# LED1.net
KiCad netlist of a schematic drawn in EAGLE
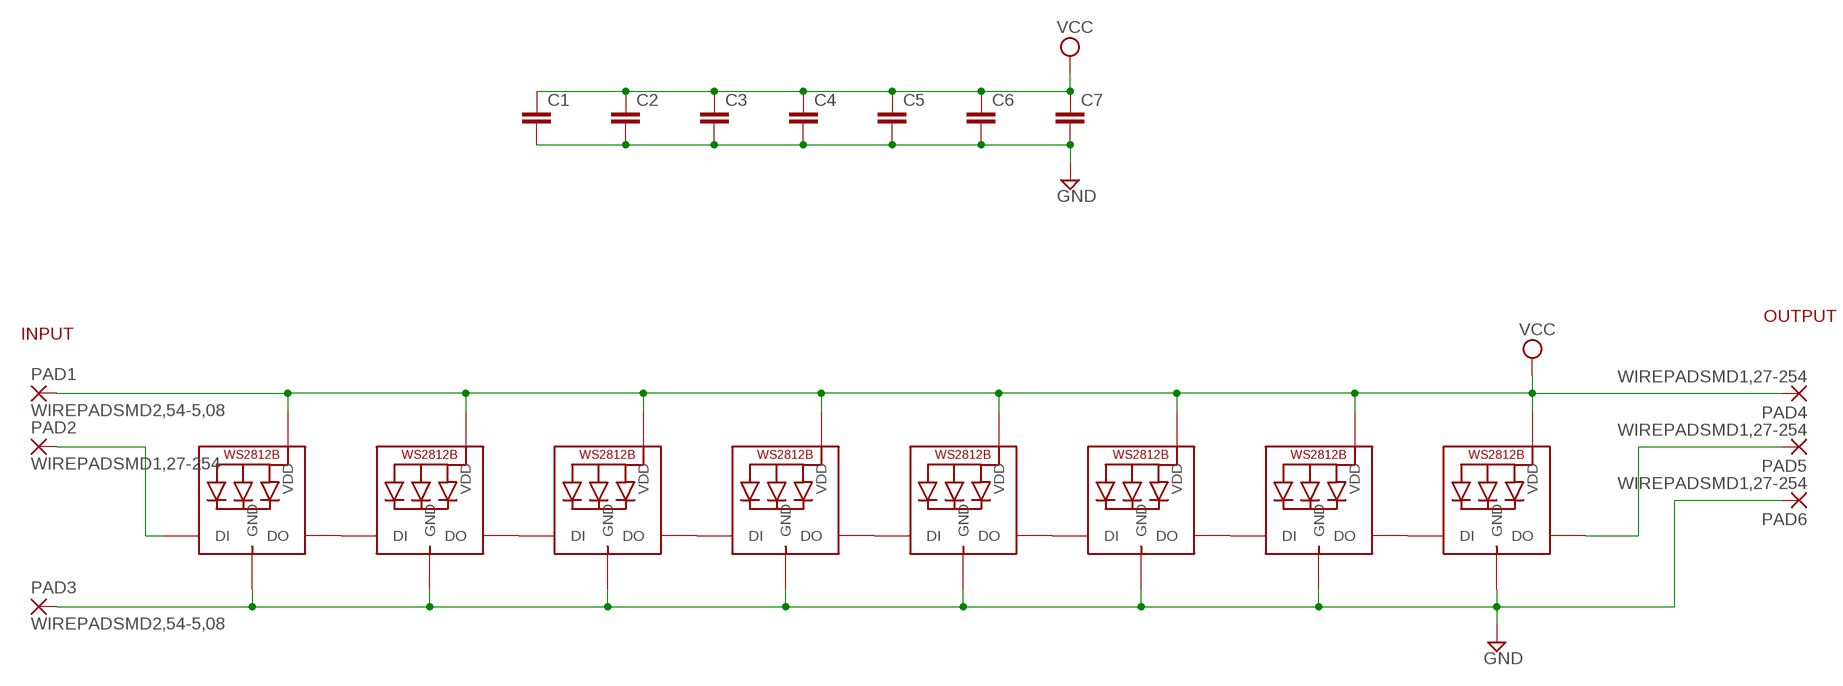
[diagram p0: schematic, sheet 1]

(export (version "E")
  (design (tool "Eeschema 10.0.6"))
  (components
    (comp (ref "C1")
      (value "C-EUC0805K")
      (footprint "eagle-import:C0805K")
      (libsource (lib "eagle-import") (part "C-EUC0805K"))
    )
    (comp (ref "C2")
      (value "C-EUC0805K")
      (footprint "eagle-import:C0805K")
      (libsource (lib "eagle-import") (part "C-EUC0805K"))
    )
    (comp (ref "C3")
      (value "C-EUC0805K")
      (footprint "eagle-import:C0805K")
      (libsource (lib "eagle-import") (part "C-EUC0805K"))
    )
    (comp (ref "C4")
      (value "C-EUC0805K")
      (footprint "eagle-import:C0805K")
      (libsource (lib "eagle-import") (part "C-EUC0805K"))
    )
    (comp (ref "C5")
      (value "C-EUC0805K")
      (footprint "eagle-import:C0805K")
      (libsource (lib "eagle-import") (part "C-EUC0805K"))
    )
    (comp (ref "C6")
      (value "C-EUC0805K")
      (footprint "eagle-import:C0805K")
      (libsource (lib "eagle-import") (part "C-EUC0805K"))
    )
    (comp (ref "C7")
      (value "C-EUC0805K")
      (footprint "eagle-import:C0805K")
      (libsource (lib "eagle-import") (part "C-EUC0805K"))
    )
    (comp (ref "LED1")
      (value "WS2812B5050")
      (footprint "eagle-import:WS2812B")
      (libsource (lib "eagle-import") (part "WS2812B5050"))
    )
    (comp (ref "LED2")
      (value "WS2812B5050")
      (footprint "eagle-import:WS2812B")
      (libsource (lib "eagle-import") (part "WS2812B5050"))
    )
    (comp (ref "LED3")
      (value "WS2812B5050")
      (footprint "eagle-import:WS2812B")
      (libsource (lib "eagle-import") (part "WS2812B5050"))
    )
    (comp (ref "LED4")
      (value "WS2812B5050")
      (footprint "eagle-import:WS2812B")
      (libsource (lib "eagle-import") (part "WS2812B5050"))
    )
    (comp (ref "LED5")
      (value "WS2812B5050")
      (footprint "eagle-import:WS2812B")
      (libsource (lib "eagle-import") (part "WS2812B5050"))
    )
    (comp (ref "LED6")
      (value "WS2812B5050")
      (footprint "eagle-import:WS2812B")
      (libsource (lib "eagle-import") (part "WS2812B5050"))
    )
    (comp (ref "LED7")
      (value "WS2812B5050")
      (footprint "eagle-import:WS2812B")
      (libsource (lib "eagle-import") (part "WS2812B5050"))
    )
    (comp (ref "LED8")
      (value "WS2812B5050")
      (footprint "eagle-import:WS2812B")
      (libsource (lib "eagle-import") (part "WS2812B5050"))
    )
    (comp (ref "PAD1")
      (value "WIREPADSMD2,54-5,08")
      (footprint "eagle-import:SMD2,54-5,08")
      (libsource (lib "eagle-import") (part "WIREPADSMD2,54-5,08"))
    )
    (comp (ref "PAD2")
      (value "WIREPADSMD1,27-254")
      (footprint "eagle-import:SMD1,27-2,54")
      (libsource (lib "eagle-import") (part "WIREPADSMD1,27-254"))
    )
    (comp (ref "PAD3")
      (value "WIREPADSMD2,54-5,08")
      (footprint "eagle-import:SMD2,54-5,08")
      (libsource (lib "eagle-import") (part "WIREPADSMD2,54-5,08"))
    )
    (comp (ref "PAD4")
      (value "WIREPADSMD1,27-254")
      (footprint "eagle-import:SMD1,27-2,54")
      (libsource (lib "eagle-import") (part "WIREPADSMD1,27-254"))
    )
    (comp (ref "PAD5")
      (value "WIREPADSMD1,27-254")
      (footprint "eagle-import:SMD1,27-2,54")
      (libsource (lib "eagle-import") (part "WIREPADSMD1,27-254"))
    )
    (comp (ref "PAD6")
      (value "WIREPADSMD1,27-254")
      (footprint "eagle-import:SMD1,27-2,54")
      (libsource (lib "eagle-import") (part "WIREPADSMD1,27-254"))
    )
  )
  (nets
    (net (code "1") (name "GND") (class "Default")
      (node (ref "C1") (pin "2") (pinfunction "2_2") (pintype "passive"))
      (node (ref "C2") (pin "2") (pinfunction "2_2") (pintype "passive"))
      (node (ref "C3") (pin "2") (pinfunction "2_2") (pintype "passive"))
      (node (ref "C4") (pin "2") (pinfunction "2_2") (pintype "passive"))
      (node (ref "C5") (pin "2") (pinfunction "2_2") (pintype "passive"))
      (node (ref "C6") (pin "2") (pinfunction "2_2") (pintype "passive"))
      (node (ref "C7") (pin "2") (pinfunction "2_2") (pintype "passive"))
      (node (ref "LED1") (pin "3-GND") (pinfunction "GND_3-GND") (pintype "power_in"))
      (node (ref "LED2") (pin "3-GND") (pinfunction "GND_3-GND") (pintype "power_in"))
      (node (ref "LED3") (pin "3-GND") (pinfunction "GND_3-GND") (pintype "power_in"))
      (node (ref "LED4") (pin "3-GND") (pinfunction "GND_3-GND") (pintype "power_in"))
      (node (ref "LED5") (pin "3-GND") (pinfunction "GND_3-GND") (pintype "power_in"))
      (node (ref "LED6") (pin "3-GND") (pinfunction "GND_3-GND") (pintype "power_in"))
      (node (ref "LED7") (pin "3-GND") (pinfunction "GND_3-GND") (pintype "power_in"))
      (node (ref "LED8") (pin "3-GND") (pinfunction "GND_3-GND") (pintype "power_in"))
      (node (ref "PAD3") (pin "1") (pinfunction "P_1") (pintype "passive"))
      (node (ref "PAD6") (pin "1") (pinfunction "P_1") (pintype "passive"))
    )
    (net (code "2") (name "Net-(LED1-DI)") (class "Default")
      (node (ref "LED1") (pin "4-DIN") (pinfunction "DI_4-DIN") (pintype "input"))
      (node (ref "PAD2") (pin "1") (pinfunction "P_1") (pintype "passive"))
    )
    (net (code "3") (name "Net-(LED1-DO)") (class "Default")
      (node (ref "LED1") (pin "2-DOUT") (pinfunction "DO_2-DOUT") (pintype "output"))
      (node (ref "LED2") (pin "4-DIN") (pinfunction "DI_4-DIN") (pintype "input"))
    )
    (net (code "4") (name "Net-(LED2-DO)") (class "Default")
      (node (ref "LED2") (pin "2-DOUT") (pinfunction "DO_2-DOUT") (pintype "output"))
      (node (ref "LED3") (pin "4-DIN") (pinfunction "DI_4-DIN") (pintype "input"))
    )
    (net (code "5") (name "Net-(LED3-DO)") (class "Default")
      (node (ref "LED3") (pin "2-DOUT") (pinfunction "DO_2-DOUT") (pintype "output"))
      (node (ref "LED4") (pin "4-DIN") (pinfunction "DI_4-DIN") (pintype "input"))
    )
    (net (code "6") (name "Net-(LED4-DO)") (class "Default")
      (node (ref "LED4") (pin "2-DOUT") (pinfunction "DO_2-DOUT") (pintype "output"))
      (node (ref "LED5") (pin "4-DIN") (pinfunction "DI_4-DIN") (pintype "input"))
    )
    (net (code "7") (name "Net-(LED5-DO)") (class "Default")
      (node (ref "LED5") (pin "2-DOUT") (pinfunction "DO_2-DOUT") (pintype "output"))
      (node (ref "LED6") (pin "4-DIN") (pinfunction "DI_4-DIN") (pintype "input"))
    )
    (net (code "8") (name "Net-(LED6-DO)") (class "Default")
      (node (ref "LED6") (pin "2-DOUT") (pinfunction "DO_2-DOUT") (pintype "output"))
      (node (ref "LED7") (pin "4-DIN") (pinfunction "DI_4-DIN") (pintype "input"))
    )
    (net (code "9") (name "Net-(LED7-DO)") (class "Default")
      (node (ref "LED7") (pin "2-DOUT") (pinfunction "DO_2-DOUT") (pintype "output"))
      (node (ref "LED8") (pin "4-DIN") (pinfunction "DI_4-DIN") (pintype "input"))
    )
    (net (code "10") (name "Net-(LED8-DO)") (class "Default")
      (node (ref "LED8") (pin "2-DOUT") (pinfunction "DO_2-DOUT") (pintype "output"))
      (node (ref "PAD5") (pin "1") (pinfunction "P_1") (pintype "passive"))
    )
    (net (code "11") (name "VCC") (class "Default")
      (node (ref "C1") (pin "1") (pinfunction "1_1") (pintype "passive"))
      (node (ref "C2") (pin "1") (pinfunction "1_1") (pintype "passive"))
      (node (ref "C3") (pin "1") (pinfunction "1_1") (pintype "passive"))
      (node (ref "C4") (pin "1") (pinfunction "1_1") (pintype "passive"))
      (node (ref "C5") (pin "1") (pinfunction "1_1") (pintype "passive"))
      (node (ref "C6") (pin "1") (pinfunction "1_1") (pintype "passive"))
      (node (ref "C7") (pin "1") (pinfunction "1_1") (pintype "passive"))
      (node (ref "LED1") (pin "1-VDD") (pinfunction "VDD_1-VDD") (pintype "power_in"))
      (node (ref "LED2") (pin "1-VDD") (pinfunction "VDD_1-VDD") (pintype "power_in"))
      (node (ref "LED3") (pin "1-VDD") (pinfunction "VDD_1-VDD") (pintype "power_in"))
      (node (ref "LED4") (pin "1-VDD") (pinfunction "VDD_1-VDD") (pintype "power_in"))
      (node (ref "LED5") (pin "1-VDD") (pinfunction "VDD_1-VDD") (pintype "power_in"))
      (node (ref "LED6") (pin "1-VDD") (pinfunction "VDD_1-VDD") (pintype "power_in"))
      (node (ref "LED7") (pin "1-VDD") (pinfunction "VDD_1-VDD") (pintype "power_in"))
      (node (ref "LED8") (pin "1-VDD") (pinfunction "VDD_1-VDD") (pintype "power_in"))
      (node (ref "PAD1") (pin "1") (pinfunction "P_1") (pintype "passive"))
      (node (ref "PAD4") (pin "1") (pinfunction "P_1") (pintype "passive"))
    )
  )
)
